# ElectroMagnet_Rev2.net
KiCad netlist of a schematic drawn in EAGLE
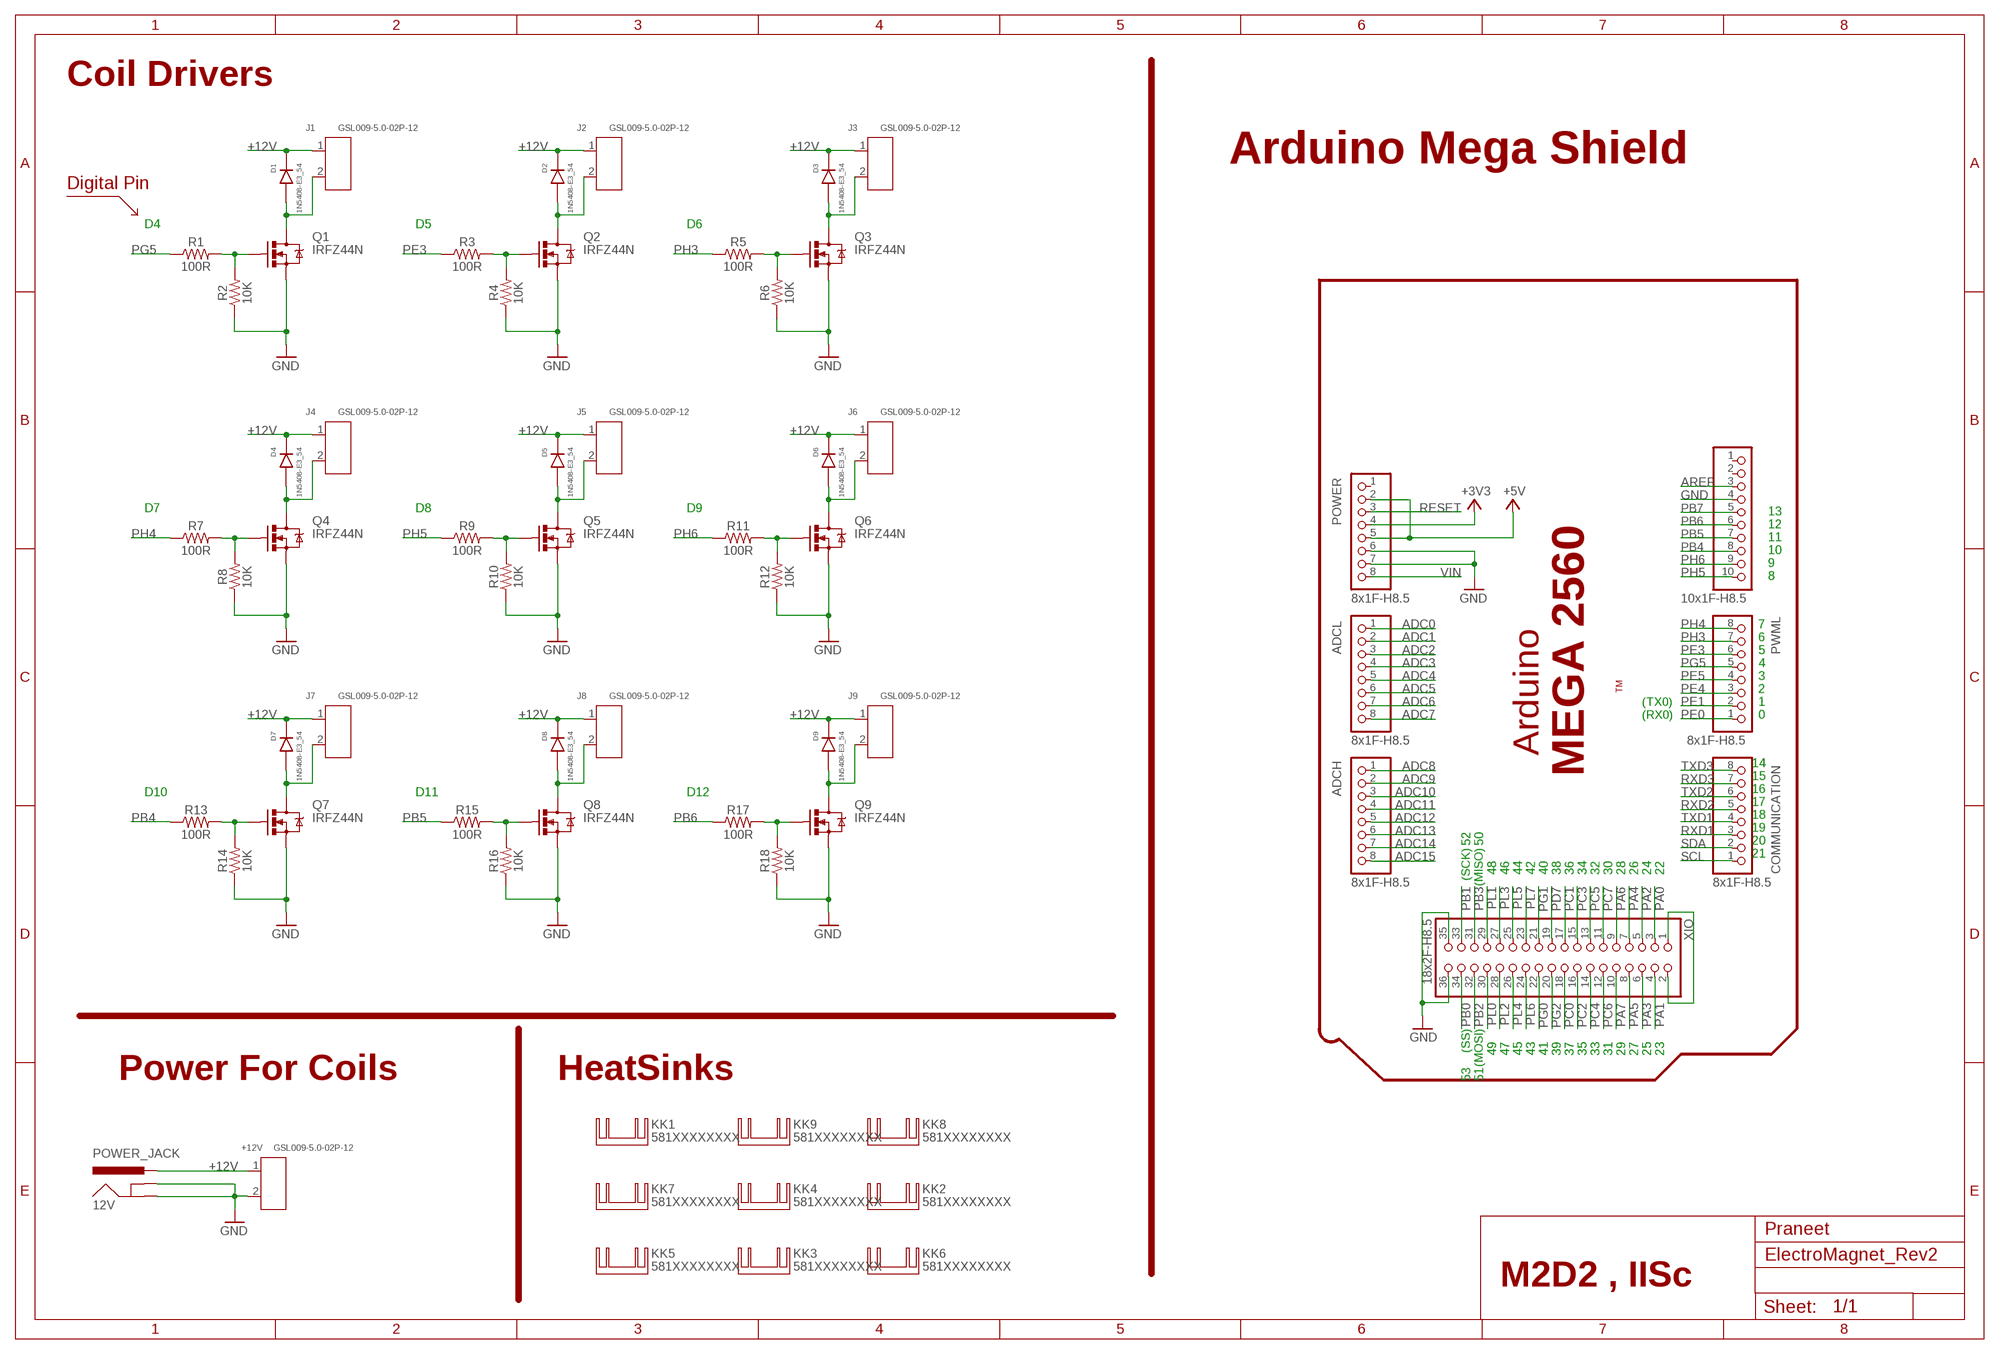
[diagram p0: schematic, sheet 1]

(export (version "E")
  (design (tool "Eeschema 10.0.6"))
  (components
    (comp (ref "+12V")
      (value "GSL009-5.0-02P-12")
      (footprint "eagle-import:H2-5.0-10.5X8.0MM")
      (libsource (lib "eagle-import") (part "SCREW-TERMINAL-BLUE(2P-5.0)"))
    )
    (comp (ref "12V")
      (value "POWER_JACK")
      (footprint "eagle-import:POWER_JACK_PTH")
      (libsource (lib "eagle-import") (part "POWER_JACK"))
    )
    (comp (ref "ADCH")
      (value "8x1F-H8.5")
      (footprint "eagle-import:1X08")
      (libsource (lib "eagle-import") (part "PINHD-1X8"))
    )
    (comp (ref "ADCL")
      (value "8x1F-H8.5")
      (footprint "eagle-import:1X08")
      (libsource (lib "eagle-import") (part "PINHD-1X8"))
    )
    (comp (ref "COMMUNICATION")
      (value "8x1F-H8.5")
      (footprint "eagle-import:1X08")
      (libsource (lib "eagle-import") (part "PINHD-1X8"))
    )
    (comp (ref "D1")
      (value "1N5408-E3_54")
      (footprint "eagle-import:DIOAD2855W132L835D505")
      (fields
        (field (name "MANUFACTURER_PART_NUMBER") "1N5408-E3/54")
        (field (name "MOUSER_PART_NUMBER") "625-1N5408-E3")
        (field (name "RS_PART_NUMBER") "6289502P")
      )
      (libsource (lib "eagle-import") (part "1N5408-E3_54"))
    )
    (comp (ref "D2")
      (value "1N5408-E3_54")
      (footprint "eagle-import:DIOAD2855W132L835D505")
      (fields
        (field (name "MANUFACTURER_PART_NUMBER") "1N5408-E3/54")
        (field (name "MOUSER_PART_NUMBER") "625-1N5408-E3")
        (field (name "RS_PART_NUMBER") "6289502P")
      )
      (libsource (lib "eagle-import") (part "1N5408-E3_54"))
    )
    (comp (ref "D3")
      (value "1N5408-E3_54")
      (footprint "eagle-import:DIOAD2855W132L835D505")
      (fields
        (field (name "MANUFACTURER_PART_NUMBER") "1N5408-E3/54")
        (field (name "MOUSER_PART_NUMBER") "625-1N5408-E3")
        (field (name "RS_PART_NUMBER") "6289502P")
      )
      (libsource (lib "eagle-import") (part "1N5408-E3_54"))
    )
    (comp (ref "D4")
      (value "1N5408-E3_54")
      (footprint "eagle-import:DIOAD2855W132L835D505")
      (fields
        (field (name "MANUFACTURER_PART_NUMBER") "1N5408-E3/54")
        (field (name "MOUSER_PART_NUMBER") "625-1N5408-E3")
        (field (name "RS_PART_NUMBER") "6289502P")
      )
      (libsource (lib "eagle-import") (part "1N5408-E3_54"))
    )
    (comp (ref "D5")
      (value "1N5408-E3_54")
      (footprint "eagle-import:DIOAD2855W132L835D505")
      (fields
        (field (name "MANUFACTURER_PART_NUMBER") "1N5408-E3/54")
        (field (name "MOUSER_PART_NUMBER") "625-1N5408-E3")
        (field (name "RS_PART_NUMBER") "6289502P")
      )
      (libsource (lib "eagle-import") (part "1N5408-E3_54"))
    )
    (comp (ref "D6")
      (value "1N5408-E3_54")
      (footprint "eagle-import:DIOAD2855W132L835D505")
      (fields
        (field (name "MANUFACTURER_PART_NUMBER") "1N5408-E3/54")
        (field (name "MOUSER_PART_NUMBER") "625-1N5408-E3")
        (field (name "RS_PART_NUMBER") "6289502P")
      )
      (libsource (lib "eagle-import") (part "1N5408-E3_54"))
    )
    (comp (ref "D7")
      (value "1N5408-E3_54")
      (footprint "eagle-import:DIOAD2855W132L835D505")
      (fields
        (field (name "MANUFACTURER_PART_NUMBER") "1N5408-E3/54")
        (field (name "MOUSER_PART_NUMBER") "625-1N5408-E3")
        (field (name "RS_PART_NUMBER") "6289502P")
      )
      (libsource (lib "eagle-import") (part "1N5408-E3_54"))
    )
    (comp (ref "D8")
      (value "1N5408-E3_54")
      (footprint "eagle-import:DIOAD2855W132L835D505")
      (fields
        (field (name "MANUFACTURER_PART_NUMBER") "1N5408-E3/54")
        (field (name "MOUSER_PART_NUMBER") "625-1N5408-E3")
        (field (name "RS_PART_NUMBER") "6289502P")
      )
      (libsource (lib "eagle-import") (part "1N5408-E3_54"))
    )
    (comp (ref "D9")
      (value "1N5408-E3_54")
      (footprint "eagle-import:DIOAD2855W132L835D505")
      (fields
        (field (name "MANUFACTURER_PART_NUMBER") "1N5408-E3/54")
        (field (name "MOUSER_PART_NUMBER") "625-1N5408-E3")
        (field (name "RS_PART_NUMBER") "6289502P")
      )
      (libsource (lib "eagle-import") (part "1N5408-E3_54"))
    )
    (comp (ref "J1")
      (value "GSL009-5.0-02P-12")
      (footprint "eagle-import:H2-5.0-10.5X8.0MM")
      (libsource (lib "eagle-import") (part "SCREW-TERMINAL-BLUE(2P-5.0)"))
    )
    (comp (ref "J2")
      (value "GSL009-5.0-02P-12")
      (footprint "eagle-import:H2-5.0-10.5X8.0MM")
      (libsource (lib "eagle-import") (part "SCREW-TERMINAL-BLUE(2P-5.0)"))
    )
    (comp (ref "J3")
      (value "GSL009-5.0-02P-12")
      (footprint "eagle-import:H2-5.0-10.5X8.0MM")
      (libsource (lib "eagle-import") (part "SCREW-TERMINAL-BLUE(2P-5.0)"))
    )
    (comp (ref "J4")
      (value "GSL009-5.0-02P-12")
      (footprint "eagle-import:H2-5.0-10.5X8.0MM")
      (libsource (lib "eagle-import") (part "SCREW-TERMINAL-BLUE(2P-5.0)"))
    )
    (comp (ref "J5")
      (value "GSL009-5.0-02P-12")
      (footprint "eagle-import:H2-5.0-10.5X8.0MM")
      (libsource (lib "eagle-import") (part "SCREW-TERMINAL-BLUE(2P-5.0)"))
    )
    (comp (ref "J6")
      (value "GSL009-5.0-02P-12")
      (footprint "eagle-import:H2-5.0-10.5X8.0MM")
      (libsource (lib "eagle-import") (part "SCREW-TERMINAL-BLUE(2P-5.0)"))
    )
    (comp (ref "J7")
      (value "GSL009-5.0-02P-12")
      (footprint "eagle-import:H2-5.0-10.5X8.0MM")
      (libsource (lib "eagle-import") (part "SCREW-TERMINAL-BLUE(2P-5.0)"))
    )
    (comp (ref "J8")
      (value "GSL009-5.0-02P-12")
      (footprint "eagle-import:H2-5.0-10.5X8.0MM")
      (libsource (lib "eagle-import") (part "SCREW-TERMINAL-BLUE(2P-5.0)"))
    )
    (comp (ref "J9")
      (value "GSL009-5.0-02P-12")
      (footprint "eagle-import:H2-5.0-10.5X8.0MM")
      (libsource (lib "eagle-import") (part "SCREW-TERMINAL-BLUE(2P-5.0)"))
    )
    (comp (ref "JP6")
      (value "10x1F-H8.5")
      (footprint "eagle-import:1X10")
      (libsource (lib "eagle-import") (part "PINHD-1X10_ARD"))
    )
    (comp (ref "KK1")
      (value "581XXXXXXXX")
      (footprint "eagle-import:581XXXXXXXX")
      (libsource (lib "eagle-import") (part "581XXXXXXXX"))
    )
    (comp (ref "KK2")
      (value "581XXXXXXXX")
      (footprint "eagle-import:581XXXXXXXX")
      (libsource (lib "eagle-import") (part "581XXXXXXXX"))
    )
    (comp (ref "KK3")
      (value "581XXXXXXXX")
      (footprint "eagle-import:581XXXXXXXX")
      (libsource (lib "eagle-import") (part "581XXXXXXXX"))
    )
    (comp (ref "KK4")
      (value "581XXXXXXXX")
      (footprint "eagle-import:581XXXXXXXX")
      (libsource (lib "eagle-import") (part "581XXXXXXXX"))
    )
    (comp (ref "KK5")
      (value "581XXXXXXXX")
      (footprint "eagle-import:581XXXXXXXX")
      (libsource (lib "eagle-import") (part "581XXXXXXXX"))
    )
    (comp (ref "KK6")
      (value "581XXXXXXXX")
      (footprint "eagle-import:581XXXXXXXX")
      (libsource (lib "eagle-import") (part "581XXXXXXXX"))
    )
    (comp (ref "KK7")
      (value "581XXXXXXXX")
      (footprint "eagle-import:581XXXXXXXX")
      (libsource (lib "eagle-import") (part "581XXXXXXXX"))
    )
    (comp (ref "KK8")
      (value "581XXXXXXXX")
      (footprint "eagle-import:581XXXXXXXX")
      (libsource (lib "eagle-import") (part "581XXXXXXXX"))
    )
    (comp (ref "KK9")
      (value "581XXXXXXXX")
      (footprint "eagle-import:581XXXXXXXX")
      (libsource (lib "eagle-import") (part "581XXXXXXXX"))
    )
    (comp (ref "POWER")
      (value "8x1F-H8.5")
      (footprint "eagle-import:1X08")
      (libsource (lib "eagle-import") (part "PINHD-1X8"))
    )
    (comp (ref "PWML")
      (value "8x1F-H8.5")
      (footprint "eagle-import:1X08")
      (libsource (lib "eagle-import") (part "PINHD-1X8"))
    )
    (comp (ref "Q1")
      (value "IRFZ44N")
      (footprint "eagle-import:TO-220")
      (fields (field (name "MF") "International Rectifier"))
      (libsource (lib "eagle-import") (part "IRFZ44N"))
    )
    (comp (ref "Q2")
      (value "IRFZ44N")
      (footprint "eagle-import:TO-220")
      (fields (field (name "MF") "International Rectifier"))
      (libsource (lib "eagle-import") (part "IRFZ44N"))
    )
    (comp (ref "Q3")
      (value "IRFZ44N")
      (footprint "eagle-import:TO-220")
      (fields (field (name "MF") "International Rectifier"))
      (libsource (lib "eagle-import") (part "IRFZ44N"))
    )
    (comp (ref "Q4")
      (value "IRFZ44N")
      (footprint "eagle-import:TO-220")
      (fields (field (name "MF") "International Rectifier"))
      (libsource (lib "eagle-import") (part "IRFZ44N"))
    )
    (comp (ref "Q5")
      (value "IRFZ44N")
      (footprint "eagle-import:TO-220")
      (fields (field (name "MF") "International Rectifier"))
      (libsource (lib "eagle-import") (part "IRFZ44N"))
    )
    (comp (ref "Q6")
      (value "IRFZ44N")
      (footprint "eagle-import:TO-220")
      (fields (field (name "MF") "International Rectifier"))
      (libsource (lib "eagle-import") (part "IRFZ44N"))
    )
    (comp (ref "Q7")
      (value "IRFZ44N")
      (footprint "eagle-import:TO-220")
      (fields (field (name "MF") "International Rectifier"))
      (libsource (lib "eagle-import") (part "IRFZ44N"))
    )
    (comp (ref "Q8")
      (value "IRFZ44N")
      (footprint "eagle-import:TO-220")
      (fields (field (name "MF") "International Rectifier"))
      (libsource (lib "eagle-import") (part "IRFZ44N"))
    )
    (comp (ref "Q9")
      (value "IRFZ44N")
      (footprint "eagle-import:TO-220")
      (fields (field (name "MF") "International Rectifier"))
      (libsource (lib "eagle-import") (part "IRFZ44N"))
    )
    (comp (ref "R1")
      (value "100R")
      (footprint "eagle-import:AXIAL-0.3")
      (libsource (lib "eagle-import") (part "RESISTORAXIAL-0.3"))
    )
    (comp (ref "R2")
      (value "10K")
      (footprint "eagle-import:AXIAL-0.3")
      (libsource (lib "eagle-import") (part "RESISTORAXIAL-0.3"))
    )
    (comp (ref "R3")
      (value "100R")
      (footprint "eagle-import:AXIAL-0.3")
      (libsource (lib "eagle-import") (part "RESISTORAXIAL-0.3"))
    )
    (comp (ref "R4")
      (value "10K")
      (footprint "eagle-import:AXIAL-0.3")
      (libsource (lib "eagle-import") (part "RESISTORAXIAL-0.3"))
    )
    (comp (ref "R5")
      (value "100R")
      (footprint "eagle-import:AXIAL-0.3")
      (libsource (lib "eagle-import") (part "RESISTORAXIAL-0.3"))
    )
    (comp (ref "R6")
      (value "10K")
      (footprint "eagle-import:AXIAL-0.3")
      (libsource (lib "eagle-import") (part "RESISTORAXIAL-0.3"))
    )
    (comp (ref "R7")
      (value "100R")
      (footprint "eagle-import:AXIAL-0.3")
      (libsource (lib "eagle-import") (part "RESISTORAXIAL-0.3"))
    )
    (comp (ref "R8")
      (value "10K")
      (footprint "eagle-import:AXIAL-0.3")
      (libsource (lib "eagle-import") (part "RESISTORAXIAL-0.3"))
    )
    (comp (ref "R9")
      (value "100R")
      (footprint "eagle-import:AXIAL-0.3")
      (libsource (lib "eagle-import") (part "RESISTORAXIAL-0.3"))
    )
    (comp (ref "R10")
      (value "10K")
      (footprint "eagle-import:AXIAL-0.3")
      (libsource (lib "eagle-import") (part "RESISTORAXIAL-0.3"))
    )
    (comp (ref "R11")
      (value "100R")
      (footprint "eagle-import:AXIAL-0.3")
      (libsource (lib "eagle-import") (part "RESISTORAXIAL-0.3"))
    )
    (comp (ref "R12")
      (value "10K")
      (footprint "eagle-import:AXIAL-0.3")
      (libsource (lib "eagle-import") (part "RESISTORAXIAL-0.3"))
    )
    (comp (ref "R13")
      (value "100R")
      (footprint "eagle-import:AXIAL-0.3")
      (libsource (lib "eagle-import") (part "RESISTORAXIAL-0.3"))
    )
    (comp (ref "R14")
      (value "10K")
      (footprint "eagle-import:AXIAL-0.3")
      (libsource (lib "eagle-import") (part "RESISTORAXIAL-0.3"))
    )
    (comp (ref "R15")
      (value "100R")
      (footprint "eagle-import:AXIAL-0.3")
      (libsource (lib "eagle-import") (part "RESISTORAXIAL-0.3"))
    )
    (comp (ref "R16")
      (value "10K")
      (footprint "eagle-import:AXIAL-0.3")
      (libsource (lib "eagle-import") (part "RESISTORAXIAL-0.3"))
    )
    (comp (ref "R17")
      (value "100R")
      (footprint "eagle-import:AXIAL-0.3")
      (libsource (lib "eagle-import") (part "RESISTORAXIAL-0.3"))
    )
    (comp (ref "R18")
      (value "10K")
      (footprint "eagle-import:AXIAL-0.3")
      (libsource (lib "eagle-import") (part "RESISTORAXIAL-0.3"))
    )
    (comp (ref "XIO")
      (value "18x2F-H8.5")
      (footprint "eagle-import:2X18")
      (libsource (lib "eagle-import") (part "PINHD-2X18"))
    )
  )
  (nets
    (net (code "1") (name "+3V3") (class "Default")
      (node (ref "POWER") (pin "4") (pinfunction "4_4") (pintype "passive"))
    )
    (net (code "2") (name "+5V") (class "Default")
      (node (ref "POWER") (pin "2") (pinfunction "2_2") (pintype "passive"))
      (node (ref "POWER") (pin "5") (pinfunction "5_5") (pintype "passive"))
    )
    (net (code "3") (name "/+12V") (class "Default")
      (node (ref "+12V") (pin "1") (pinfunction "1_1") (pintype "bidirectional"))
      (node (ref "12V") (pin "PWR") (pinfunction "PWR_PWR") (pintype "bidirectional"))
      (node (ref "D1") (pin "1") (pinfunction "K_1") (pintype "bidirectional"))
      (node (ref "D2") (pin "1") (pinfunction "K_1") (pintype "bidirectional"))
      (node (ref "D3") (pin "1") (pinfunction "K_1") (pintype "bidirectional"))
      (node (ref "D4") (pin "1") (pinfunction "K_1") (pintype "bidirectional"))
      (node (ref "D5") (pin "1") (pinfunction "K_1") (pintype "bidirectional"))
      (node (ref "D6") (pin "1") (pinfunction "K_1") (pintype "bidirectional"))
      (node (ref "D7") (pin "1") (pinfunction "K_1") (pintype "bidirectional"))
      (node (ref "D8") (pin "1") (pinfunction "K_1") (pintype "bidirectional"))
      (node (ref "D9") (pin "1") (pinfunction "K_1") (pintype "bidirectional"))
      (node (ref "J1") (pin "1") (pinfunction "1_1") (pintype "bidirectional"))
      (node (ref "J2") (pin "1") (pinfunction "1_1") (pintype "bidirectional"))
      (node (ref "J3") (pin "1") (pinfunction "1_1") (pintype "bidirectional"))
      (node (ref "J4") (pin "1") (pinfunction "1_1") (pintype "bidirectional"))
      (node (ref "J5") (pin "1") (pinfunction "1_1") (pintype "bidirectional"))
      (node (ref "J6") (pin "1") (pinfunction "1_1") (pintype "bidirectional"))
      (node (ref "J7") (pin "1") (pinfunction "1_1") (pintype "bidirectional"))
      (node (ref "J8") (pin "1") (pinfunction "1_1") (pintype "bidirectional"))
      (node (ref "J9") (pin "1") (pinfunction "1_1") (pintype "bidirectional"))
    )
    (net (code "4") (name "/ADC0") (class "Default")
      (node (ref "ADCL") (pin "1") (pinfunction "1_1") (pintype "passive"))
    )
    (net (code "5") (name "/ADC1") (class "Default")
      (node (ref "ADCL") (pin "2") (pinfunction "2_2") (pintype "passive"))
    )
    (net (code "6") (name "/ADC2") (class "Default")
      (node (ref "ADCL") (pin "3") (pinfunction "3_3") (pintype "passive"))
    )
    (net (code "7") (name "/ADC3") (class "Default")
      (node (ref "ADCL") (pin "4") (pinfunction "4_4") (pintype "passive"))
    )
    (net (code "8") (name "/ADC4") (class "Default")
      (node (ref "ADCL") (pin "5") (pinfunction "5_5") (pintype "passive"))
    )
    (net (code "9") (name "/ADC5") (class "Default")
      (node (ref "ADCL") (pin "6") (pinfunction "6_6") (pintype "passive"))
    )
    (net (code "10") (name "/ADC6") (class "Default")
      (node (ref "ADCL") (pin "7") (pinfunction "7_7") (pintype "passive"))
    )
    (net (code "11") (name "/ADC7") (class "Default")
      (node (ref "ADCL") (pin "8") (pinfunction "8_8") (pintype "passive"))
    )
    (net (code "12") (name "/ADC8") (class "Default")
      (node (ref "ADCH") (pin "1") (pinfunction "1_1") (pintype "passive"))
    )
    (net (code "13") (name "/ADC9") (class "Default")
      (node (ref "ADCH") (pin "2") (pinfunction "2_2") (pintype "passive"))
    )
    (net (code "14") (name "/ADC10") (class "Default")
      (node (ref "ADCH") (pin "3") (pinfunction "3_3") (pintype "passive"))
    )
    (net (code "15") (name "/ADC11") (class "Default")
      (node (ref "ADCH") (pin "4") (pinfunction "4_4") (pintype "passive"))
    )
    (net (code "16") (name "/ADC12") (class "Default")
      (node (ref "ADCH") (pin "5") (pinfunction "5_5") (pintype "passive"))
    )
    (net (code "17") (name "/ADC13") (class "Default")
      (node (ref "ADCH") (pin "6") (pinfunction "6_6") (pintype "passive"))
    )
    (net (code "18") (name "/ADC14") (class "Default")
      (node (ref "ADCH") (pin "7") (pinfunction "7_7") (pintype "passive"))
    )
    (net (code "19") (name "/ADC15") (class "Default")
      (node (ref "ADCH") (pin "8") (pinfunction "8_8") (pintype "passive"))
    )
    (net (code "20") (name "/AREF") (class "Default")
      (node (ref "JP6") (pin "3") (pinfunction "3_3") (pintype "passive"))
    )
    (net (code "21") (name "/PA0") (class "Default")
      (node (ref "XIO") (pin "3") (pinfunction "3_3") (pintype "passive"))
    )
    (net (code "22") (name "/PA1") (class "Default")
      (node (ref "XIO") (pin "4") (pinfunction "4_4") (pintype "passive"))
    )
    (net (code "23") (name "/PA2") (class "Default")
      (node (ref "XIO") (pin "5") (pinfunction "5_5") (pintype "passive"))
    )
    (net (code "24") (name "/PA3") (class "Default")
      (node (ref "XIO") (pin "6") (pinfunction "6_6") (pintype "passive"))
    )
    (net (code "25") (name "/PA4") (class "Default")
      (node (ref "XIO") (pin "7") (pinfunction "7_7") (pintype "passive"))
    )
    (net (code "26") (name "/PA5") (class "Default")
      (node (ref "XIO") (pin "8") (pinfunction "8_8") (pintype "passive"))
    )
    (net (code "27") (name "/PA6") (class "Default")
      (node (ref "XIO") (pin "9") (pinfunction "9_9") (pintype "passive"))
    )
    (net (code "28") (name "/PA7") (class "Default")
      (node (ref "XIO") (pin "10") (pinfunction "10_10") (pintype "passive"))
    )
    (net (code "29") (name "/PB0") (class "Default")
      (node (ref "XIO") (pin "34") (pinfunction "34_34") (pintype "passive"))
    )
    (net (code "30") (name "/PB1") (class "Default")
      (node (ref "XIO") (pin "33") (pinfunction "33_33") (pintype "passive"))
    )
    (net (code "31") (name "/PB2") (class "Default")
      (node (ref "XIO") (pin "32") (pinfunction "32_32") (pintype "passive"))
    )
    (net (code "32") (name "/PB3") (class "Default")
      (node (ref "XIO") (pin "31") (pinfunction "31_31") (pintype "passive"))
    )
    (net (code "33") (name "/PB4") (class "Default")
      (node (ref "JP6") (pin "8") (pinfunction "8_8") (pintype "passive"))
      (node (ref "R13") (pin "P$1") (pinfunction "1_P$1") (pintype "passive"))
    )
    (net (code "34") (name "/PB5") (class "Default")
      (node (ref "JP6") (pin "7") (pinfunction "7_7") (pintype "passive"))
      (node (ref "R15") (pin "P$1") (pinfunction "1_P$1") (pintype "passive"))
    )
    (net (code "35") (name "/PB6") (class "Default")
      (node (ref "JP6") (pin "6") (pinfunction "6_6") (pintype "passive"))
      (node (ref "R17") (pin "P$1") (pinfunction "1_P$1") (pintype "passive"))
    )
    (net (code "36") (name "/PB7") (class "Default")
      (node (ref "JP6") (pin "5") (pinfunction "5_5") (pintype "passive"))
    )
    (net (code "37") (name "/PC0") (class "Default")
      (node (ref "XIO") (pin "18") (pinfunction "18_18") (pintype "passive"))
    )
    (net (code "38") (name "/PC1") (class "Default")
      (node (ref "XIO") (pin "17") (pinfunction "17_17") (pintype "passive"))
    )
    (net (code "39") (name "/PC2") (class "Default")
      (node (ref "XIO") (pin "16") (pinfunction "16_16") (pintype "passive"))
    )
    (net (code "40") (name "/PC3") (class "Default")
      (node (ref "XIO") (pin "15") (pinfunction "15_15") (pintype "passive"))
    )
    (net (code "41") (name "/PC4") (class "Default")
      (node (ref "XIO") (pin "14") (pinfunction "14_14") (pintype "passive"))
    )
    (net (code "42") (name "/PC5") (class "Default")
      (node (ref "XIO") (pin "13") (pinfunction "13_13") (pintype "passive"))
    )
    (net (code "43") (name "/PC6") (class "Default")
      (node (ref "XIO") (pin "12") (pinfunction "12_12") (pintype "passive"))
    )
    (net (code "44") (name "/PC7") (class "Default")
      (node (ref "XIO") (pin "11") (pinfunction "11_11") (pintype "passive"))
    )
    (net (code "45") (name "/PD7") (class "Default")
      (node (ref "XIO") (pin "19") (pinfunction "19_19") (pintype "passive"))
    )
    (net (code "46") (name "/PE0") (class "Default")
      (node (ref "PWML") (pin "1") (pinfunction "1_1") (pintype "passive"))
    )
    (net (code "47") (name "/PE1") (class "Default")
      (node (ref "PWML") (pin "2") (pinfunction "2_2") (pintype "passive"))
    )
    (net (code "48") (name "/PE3") (class "Default")
      (node (ref "PWML") (pin "6") (pinfunction "6_6") (pintype "passive"))
      (node (ref "R3") (pin "P$1") (pinfunction "1_P$1") (pintype "passive"))
    )
    (net (code "49") (name "/PE4") (class "Default")
      (node (ref "PWML") (pin "3") (pinfunction "3_3") (pintype "passive"))
    )
    (net (code "50") (name "/PE5") (class "Default")
      (node (ref "PWML") (pin "4") (pinfunction "4_4") (pintype "passive"))
    )
    (net (code "51") (name "/PG0") (class "Default")
      (node (ref "XIO") (pin "22") (pinfunction "22_22") (pintype "passive"))
    )
    (net (code "52") (name "/PG1") (class "Default")
      (node (ref "XIO") (pin "21") (pinfunction "21_21") (pintype "passive"))
    )
    (net (code "53") (name "/PG2") (class "Default")
      (node (ref "XIO") (pin "20") (pinfunction "20_20") (pintype "passive"))
    )
    (net (code "54") (name "/PG5") (class "Default")
      (node (ref "PWML") (pin "5") (pinfunction "5_5") (pintype "passive"))
      (node (ref "R1") (pin "P$1") (pinfunction "1_P$1") (pintype "passive"))
    )
    (net (code "55") (name "/PH3") (class "Default")
      (node (ref "PWML") (pin "7") (pinfunction "7_7") (pintype "passive"))
      (node (ref "R5") (pin "P$1") (pinfunction "1_P$1") (pintype "passive"))
    )
    (net (code "56") (name "/PH4") (class "Default")
      (node (ref "PWML") (pin "8") (pinfunction "8_8") (pintype "passive"))
      (node (ref "R7") (pin "P$1") (pinfunction "1_P$1") (pintype "passive"))
    )
    (net (code "57") (name "/PH5") (class "Default")
      (node (ref "JP6") (pin "10") (pinfunction "10_10") (pintype "passive"))
      (node (ref "R9") (pin "P$1") (pinfunction "1_P$1") (pintype "passive"))
    )
    (net (code "58") (name "/PH6") (class "Default")
      (node (ref "JP6") (pin "9") (pinfunction "9_9") (pintype "passive"))
      (node (ref "R11") (pin "P$1") (pinfunction "1_P$1") (pintype "passive"))
    )
    (net (code "59") (name "/PL0") (class "Default")
      (node (ref "XIO") (pin "30") (pinfunction "30_30") (pintype "passive"))
    )
    (net (code "60") (name "/PL1") (class "Default")
      (node (ref "XIO") (pin "29") (pinfunction "29_29") (pintype "passive"))
    )
    (net (code "61") (name "/PL2") (class "Default")
      (node (ref "XIO") (pin "28") (pinfunction "28_28") (pintype "passive"))
    )
    (net (code "62") (name "/PL3") (class "Default")
      (node (ref "XIO") (pin "27") (pinfunction "27_27") (pintype "passive"))
    )
    (net (code "63") (name "/PL4") (class "Default")
      (node (ref "XIO") (pin "26") (pinfunction "26_26") (pintype "passive"))
    )
    (net (code "64") (name "/PL5") (class "Default")
      (node (ref "XIO") (pin "25") (pinfunction "25_25") (pintype "passive"))
    )
    (net (code "65") (name "/PL6") (class "Default")
      (node (ref "XIO") (pin "24") (pinfunction "24_24") (pintype "passive"))
    )
    (net (code "66") (name "/PL7") (class "Default")
      (node (ref "XIO") (pin "23") (pinfunction "23_23") (pintype "passive"))
    )
    (net (code "67") (name "/RESET") (class "Default")
      (node (ref "POWER") (pin "3") (pinfunction "3_3") (pintype "passive"))
    )
    (net (code "68") (name "/RXD1") (class "Default")
      (node (ref "COMMUNICATION") (pin "3") (pinfunction "3_3") (pintype "passive"))
    )
    (net (code "69") (name "/RXD2") (class "Default")
      (node (ref "COMMUNICATION") (pin "5") (pinfunction "5_5") (pintype "passive"))
    )
    (net (code "70") (name "/RXD3") (class "Default")
      (node (ref "COMMUNICATION") (pin "7") (pinfunction "7_7") (pintype "passive"))
    )
    (net (code "71") (name "/SCL") (class "Default")
      (node (ref "COMMUNICATION") (pin "1") (pinfunction "1_1") (pintype "passive"))
    )
    (net (code "72") (name "/SDA") (class "Default")
      (node (ref "COMMUNICATION") (pin "2") (pinfunction "2_2") (pintype "passive"))
    )
    (net (code "73") (name "/TXD1") (class "Default")
      (node (ref "COMMUNICATION") (pin "4") (pinfunction "4_4") (pintype "passive"))
    )
    (net (code "74") (name "/TXD2") (class "Default")
      (node (ref "COMMUNICATION") (pin "6") (pinfunction "6_6") (pintype "passive"))
    )
    (net (code "75") (name "/TXD3") (class "Default")
      (node (ref "COMMUNICATION") (pin "8") (pinfunction "8_8") (pintype "passive"))
    )
    (net (code "76") (name "/VIN") (class "Default")
      (node (ref "POWER") (pin "8") (pinfunction "8_8") (pintype "passive"))
    )
    (net (code "77") (name "GND") (class "Default")
      (node (ref "+12V") (pin "2") (pinfunction "2_2") (pintype "bidirectional"))
      (node (ref "12V") (pin "GND") (pinfunction "GND_GND") (pintype "bidirectional"))
      (node (ref "12V") (pin "GNDBREAK") (pinfunction "GNDBREAK_GNDBREAK") (pintype "bidirectional"))
      (node (ref "JP6") (pin "4") (pinfunction "4_4") (pintype "passive"))
      (node (ref "POWER") (pin "6") (pinfunction "6_6") (pintype "passive"))
      (node (ref "POWER") (pin "7") (pinfunction "7_7") (pintype "passive"))
      (node (ref "Q1") (pin "3") (pinfunction "S_3") (pintype "passive"))
      (node (ref "Q2") (pin "3") (pinfunction "S_3") (pintype "passive"))
      (node (ref "Q3") (pin "3") (pinfunction "S_3") (pintype "passive"))
      (node (ref "Q4") (pin "3") (pinfunction "S_3") (pintype "passive"))
      (node (ref "Q5") (pin "3") (pinfunction "S_3") (pintype "passive"))
      (node (ref "Q6") (pin "3") (pinfunction "S_3") (pintype "passive"))
      (node (ref "Q7") (pin "3") (pinfunction "S_3") (pintype "passive"))
      (node (ref "Q8") (pin "3") (pinfunction "S_3") (pintype "passive"))
      (node (ref "Q9") (pin "3") (pinfunction "S_3") (pintype "passive"))
      (node (ref "R10") (pin "P$1") (pinfunction "1_P$1") (pintype "passive"))
      (node (ref "R12") (pin "P$1") (pinfunction "1_P$1") (pintype "passive"))
      (node (ref "R14") (pin "P$1") (pinfunction "1_P$1") (pintype "passive"))
      (node (ref "R16") (pin "P$1") (pinfunction "1_P$1") (pintype "passive"))
      (node (ref "R18") (pin "P$1") (pinfunction "1_P$1") (pintype "passive"))
      (node (ref "R2") (pin "P$1") (pinfunction "1_P$1") (pintype "passive"))
      (node (ref "R4") (pin "P$1") (pinfunction "1_P$1") (pintype "passive"))
      (node (ref "R6") (pin "P$1") (pinfunction "1_P$1") (pintype "passive"))
      (node (ref "R8") (pin "P$1") (pinfunction "1_P$1") (pintype "passive"))
      (node (ref "XIO") (pin "35") (pinfunction "35_35") (pintype "passive"))
      (node (ref "XIO") (pin "36") (pinfunction "36_36") (pintype "passive"))
    )
    (net (code "78") (name "Net-(D1-A)") (class "Default")
      (node (ref "D1") (pin "2") (pinfunction "A_2") (pintype "bidirectional"))
      (node (ref "J1") (pin "2") (pinfunction "2_2") (pintype "bidirectional"))
      (node (ref "Q1") (pin "2") (pinfunction "D_2") (pintype "passive"))
    )
    (net (code "79") (name "Net-(D2-A)") (class "Default")
      (node (ref "D2") (pin "2") (pinfunction "A_2") (pintype "bidirectional"))
      (node (ref "J2") (pin "2") (pinfunction "2_2") (pintype "bidirectional"))
      (node (ref "Q2") (pin "2") (pinfunction "D_2") (pintype "passive"))
    )
    (net (code "80") (name "Net-(D3-A)") (class "Default")
      (node (ref "D3") (pin "2") (pinfunction "A_2") (pintype "bidirectional"))
      (node (ref "J3") (pin "2") (pinfunction "2_2") (pintype "bidirectional"))
      (node (ref "Q3") (pin "2") (pinfunction "D_2") (pintype "passive"))
    )
    (net (code "81") (name "Net-(D4-A)") (class "Default")
      (node (ref "D4") (pin "2") (pinfunction "A_2") (pintype "bidirectional"))
      (node (ref "J4") (pin "2") (pinfunction "2_2") (pintype "bidirectional"))
      (node (ref "Q4") (pin "2") (pinfunction "D_2") (pintype "passive"))
    )
    (net (code "82") (name "Net-(D5-A)") (class "Default")
      (node (ref "D5") (pin "2") (pinfunction "A_2") (pintype "bidirectional"))
      (node (ref "J5") (pin "2") (pinfunction "2_2") (pintype "bidirectional"))
      (node (ref "Q5") (pin "2") (pinfunction "D_2") (pintype "passive"))
    )
    (net (code "83") (name "Net-(D6-A)") (class "Default")
      (node (ref "D6") (pin "2") (pinfunction "A_2") (pintype "bidirectional"))
      (node (ref "J6") (pin "2") (pinfunction "2_2") (pintype "bidirectional"))
      (node (ref "Q6") (pin "2") (pinfunction "D_2") (pintype "passive"))
    )
    (net (code "84") (name "Net-(D7-A)") (class "Default")
      (node (ref "D7") (pin "2") (pinfunction "A_2") (pintype "bidirectional"))
      (node (ref "J7") (pin "2") (pinfunction "2_2") (pintype "bidirectional"))
      (node (ref "Q7") (pin "2") (pinfunction "D_2") (pintype "passive"))
    )
    (net (code "85") (name "Net-(D8-A)") (class "Default")
      (node (ref "D8") (pin "2") (pinfunction "A_2") (pintype "bidirectional"))
      (node (ref "J8") (pin "2") (pinfunction "2_2") (pintype "bidirectional"))
      (node (ref "Q8") (pin "2") (pinfunction "D_2") (pintype "passive"))
    )
    (net (code "86") (name "Net-(D9-A)") (class "Default")
      (node (ref "D9") (pin "2") (pinfunction "A_2") (pintype "bidirectional"))
      (node (ref "J9") (pin "2") (pinfunction "2_2") (pintype "bidirectional"))
      (node (ref "Q9") (pin "2") (pinfunction "D_2") (pintype "passive"))
    )
    (net (code "87") (name "Net-(Q1-G)") (class "Default")
      (node (ref "Q1") (pin "1") (pinfunction "G_1") (pintype "passive"))
      (node (ref "R1") (pin "P$2") (pinfunction "2_P$2") (pintype "passive"))
      (node (ref "R2") (pin "P$2") (pinfunction "2_P$2") (pintype "passive"))
    )
    (net (code "88") (name "Net-(Q2-G)") (class "Default")
      (node (ref "Q2") (pin "1") (pinfunction "G_1") (pintype "passive"))
      (node (ref "R3") (pin "P$2") (pinfunction "2_P$2") (pintype "passive"))
      (node (ref "R4") (pin "P$2") (pinfunction "2_P$2") (pintype "passive"))
    )
    (net (code "89") (name "Net-(Q3-G)") (class "Default")
      (node (ref "Q3") (pin "1") (pinfunction "G_1") (pintype "passive"))
      (node (ref "R5") (pin "P$2") (pinfunction "2_P$2") (pintype "passive"))
      (node (ref "R6") (pin "P$2") (pinfunction "2_P$2") (pintype "passive"))
    )
    (net (code "90") (name "Net-(Q4-G)") (class "Default")
      (node (ref "Q4") (pin "1") (pinfunction "G_1") (pintype "passive"))
      (node (ref "R7") (pin "P$2") (pinfunction "2_P$2") (pintype "passive"))
      (node (ref "R8") (pin "P$2") (pinfunction "2_P$2") (pintype "passive"))
    )
    (net (code "91") (name "Net-(Q5-G)") (class "Default")
      (node (ref "Q5") (pin "1") (pinfunction "G_1") (pintype "passive"))
      (node (ref "R10") (pin "P$2") (pinfunction "2_P$2") (pintype "passive"))
      (node (ref "R9") (pin "P$2") (pinfunction "2_P$2") (pintype "passive"))
    )
    (net (code "92") (name "Net-(Q6-G)") (class "Default")
      (node (ref "Q6") (pin "1") (pinfunction "G_1") (pintype "passive"))
      (node (ref "R11") (pin "P$2") (pinfunction "2_P$2") (pintype "passive"))
      (node (ref "R12") (pin "P$2") (pinfunction "2_P$2") (pintype "passive"))
    )
    (net (code "93") (name "Net-(Q7-G)") (class "Default")
      (node (ref "Q7") (pin "1") (pinfunction "G_1") (pintype "passive"))
      (node (ref "R13") (pin "P$2") (pinfunction "2_P$2") (pintype "passive"))
      (node (ref "R14") (pin "P$2") (pinfunction "2_P$2") (pintype "passive"))
    )
    (net (code "94") (name "Net-(Q8-G)") (class "Default")
      (node (ref "Q8") (pin "1") (pinfunction "G_1") (pintype "passive"))
      (node (ref "R15") (pin "P$2") (pinfunction "2_P$2") (pintype "passive"))
      (node (ref "R16") (pin "P$2") (pinfunction "2_P$2") (pintype "passive"))
    )
    (net (code "95") (name "Net-(Q9-G)") (class "Default")
      (node (ref "Q9") (pin "1") (pinfunction "G_1") (pintype "passive"))
      (node (ref "R17") (pin "P$2") (pinfunction "2_P$2") (pintype "passive"))
      (node (ref "R18") (pin "P$2") (pinfunction "2_P$2") (pintype "passive"))
    )
    (net (code "96") (name "Net-(XIO-Pad1)") (class "Default")
      (node (ref "XIO") (pin "1") (pinfunction "1_1") (pintype "passive"))
      (node (ref "XIO") (pin "2") (pinfunction "2_2") (pintype "passive"))
    )
    (net (code "97") (name "unconnected-(JP6-Pad1)") (class "Default")
      (node (ref "JP6") (pin "1") (pinfunction "1_1") (pintype "passive"))
    )
    (net (code "98") (name "unconnected-(JP6-Pad2)") (class "Default")
      (node (ref "JP6") (pin "2") (pinfunction "2_2") (pintype "passive"))
    )
    (net (code "99") (name "unconnected-(POWER-Pad1)") (class "Default")
      (node (ref "POWER") (pin "1") (pinfunction "1_1") (pintype "passive"))
    )
  )
)
